# serial_4.net
KiCad netlist of a schematic drawn in Altium Designer
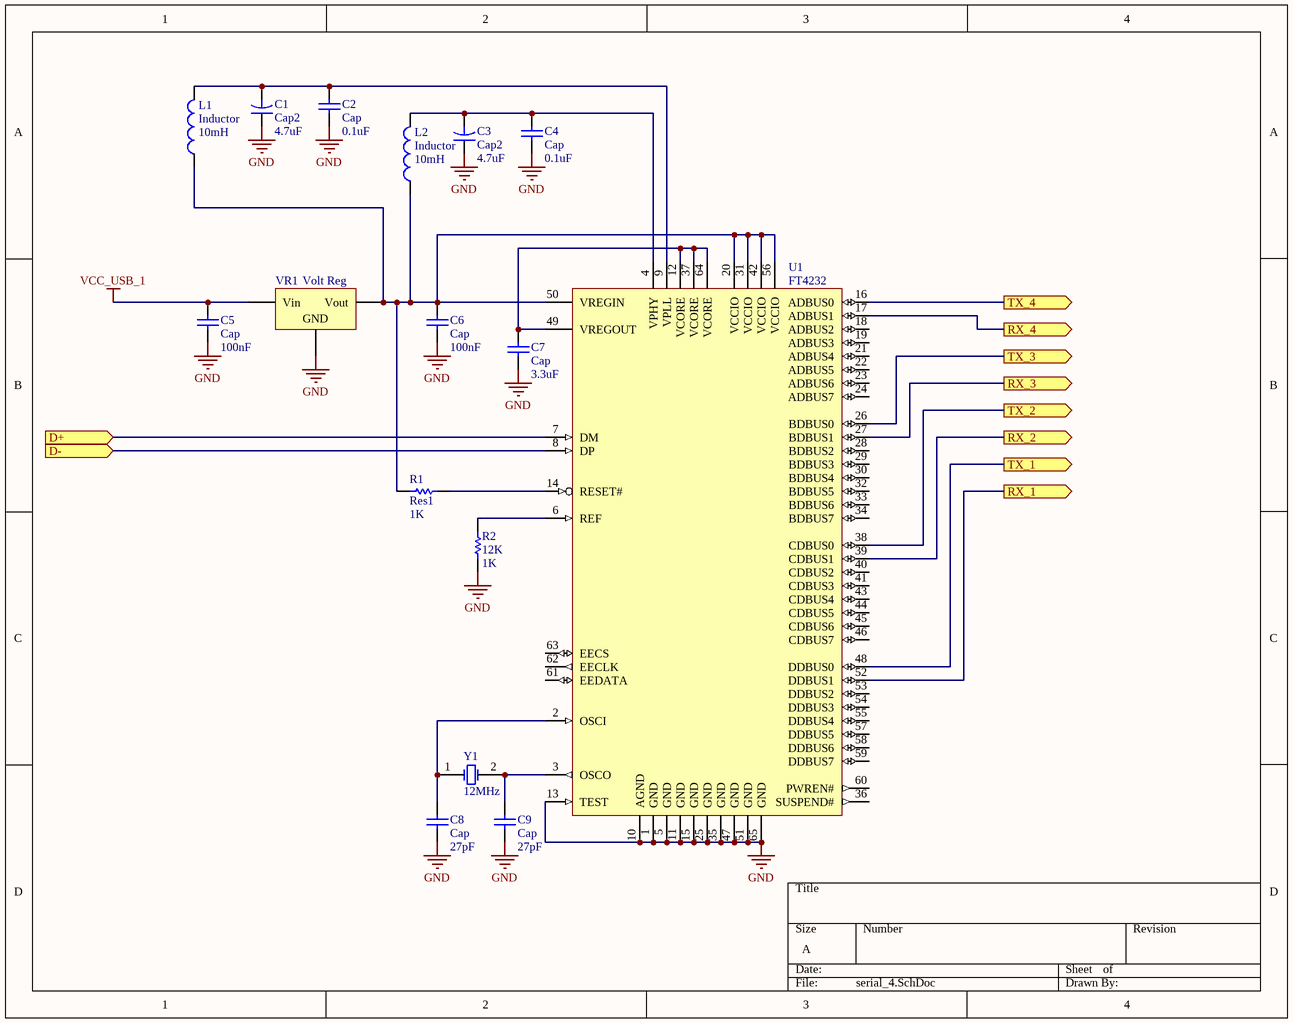
[diagram p0: serial_4.SchDoc]

(export (version "E")
  (design (tool "Eeschema 10.0.6"))
  (components
    (comp (ref "C1")
      (value "Cap2")
      (footprint "CAPR5-4X5")
      (description "Capacitor")
      (fields (field (name "ALTIUM_VALUE") "4.7uF") (field (name "PUBLISHER") "Altium Limited"))
      (libsource (lib "Miscellaneous Devices") (part "Cap2"))
    )
    (comp (ref "C2")
      (value "Cap")
      (footprint "C0805")
      (description "Capacitor")
      (fields (field (name "ALTIUM_VALUE") "0.1uF") (field (name "PUBLISHER") "Altium Limited"))
      (libsource (lib "Miscellaneous Devices") (part "Cap"))
    )
    (comp (ref "C3")
      (value "Cap2")
      (footprint "CAPR5-4X5")
      (description "Capacitor")
      (fields (field (name "ALTIUM_VALUE") "4.7uF") (field (name "PUBLISHER") "Altium Limited"))
      (libsource (lib "Miscellaneous Devices") (part "Cap2"))
    )
    (comp (ref "C4")
      (value "Cap")
      (footprint "C0805")
      (description "Capacitor")
      (fields (field (name "ALTIUM_VALUE") "0.1uF") (field (name "PUBLISHER") "Altium Limited"))
      (libsource (lib "Miscellaneous Devices") (part "Cap"))
    )
    (comp (ref "C5")
      (value "Cap")
      (footprint "C0805")
      (description "Capacitor")
      (fields (field (name "ALTIUM_VALUE") "100nF") (field (name "PUBLISHER") "Altium Limited"))
      (libsource (lib "Miscellaneous Devices") (part "Cap"))
    )
    (comp (ref "C6")
      (value "Cap")
      (footprint "C0805")
      (description "Capacitor")
      (fields (field (name "ALTIUM_VALUE") "100nF") (field (name "PUBLISHER") "Altium Limited"))
      (libsource (lib "Miscellaneous Devices") (part "Cap"))
    )
    (comp (ref "C7")
      (value "Cap")
      (footprint "C0805")
      (description "Capacitor")
      (fields (field (name "ALTIUM_VALUE") "3.3uF") (field (name "PUBLISHER") "Altium Limited"))
      (libsource (lib "Miscellaneous Devices") (part "Cap"))
    )
    (comp (ref "C8")
      (value "Cap")
      (footprint "C0805")
      (description "Capacitor")
      (fields (field (name "ALTIUM_VALUE") "27pF") (field (name "PUBLISHER") "Altium Limited"))
      (libsource (lib "Miscellaneous Devices") (part "Cap"))
    )
    (comp (ref "C9")
      (value "Cap")
      (footprint "C0805")
      (description "Capacitor")
      (fields (field (name "ALTIUM_VALUE") "27pF") (field (name "PUBLISHER") "Altium Limited"))
      (libsource (lib "Miscellaneous Devices") (part "Cap"))
    )
    (comp (ref "L1")
      (value "Inductor")
      (footprint "C0805")
      (fields (field (name "ALTIUM_VALUE") "10mH") (field (name "PUBLISHER") "Altium Limited"))
      (libsource (lib "Miscellaneous Devices") (part "Inductor"))
    )
    (comp (ref "L2")
      (value "Inductor")
      (footprint "C0805")
      (fields (field (name "ALTIUM_VALUE") "10mH") (field (name "PUBLISHER") "Altium Limited"))
      (libsource (lib "Miscellaneous Devices") (part "Inductor"))
    )
    (comp (ref "R1")
      (value "Res1")
      (footprint "0805R-1K")
      (description "Resistor")
      (fields (field (name "ALTIUM_VALUE") "1K") (field (name "PUBLISHER") "Altium Limited"))
      (libsource (lib "Miscellaneous Devices") (part "Res1"))
    )
    (comp (ref "R2")
      (value "12K")
      (footprint "0805R-12K")
      (description "Resistor")
      (fields (field (name "ALTIUM_VALUE") "1K") (field (name "PUBLISHER") "Altium Limited"))
      (libsource (lib "Miscellaneous Devices") (part "Res1"))
    )
    (comp (ref "U1")
      (value "FT4232")
      (footprint "QFN64_2_N")
      (description "Quad High Speed USB To Multipurpose UART/MPSSE IC, QFN-64, Tray")
      (fields (field (name "PUBLISHER") "Altium Limited"))
      (libsource (lib "FTDI Communication UART") (part "FT4232HQ-Tray"))
    )
    (comp (ref "VR1")
      (value "Volt Reg")
      (footprint "SOT223")
      (description "Voltage Regulator")
      (fields (field (name "PUBLISHER") "Altium Limited"))
      (libsource (lib "Miscellaneous Devices") (part "Volt Reg"))
    )
    (comp (ref "Y1")
      (value "12MHz")
      (footprint "XTAL-HC49US-7MM")
      (description "Crystal Oscillator")
      (fields (field (name "PUBLISHER") "Altium Limited"))
      (libsource (lib "Miscellaneous Devices") (part "XTAL"))
    )
  )
  (nets
    (net (code "1") (name "/D+") (class "Default")
      (node (ref "U1") (pin "7") (pinfunction "DM_7") (pintype "input"))
    )
    (net (code "2") (name "/D-") (class "Default")
      (node (ref "U1") (pin "8") (pinfunction "DP_8") (pintype "input"))
    )
    (net (code "3") (name "/RX_1") (class "Default")
      (node (ref "U1") (pin "52") (pinfunction "DDBUS1_52") (pintype "bidirectional"))
    )
    (net (code "4") (name "/RX_2") (class "Default")
      (node (ref "U1") (pin "39") (pinfunction "CDBUS1_39") (pintype "bidirectional"))
    )
    (net (code "5") (name "/RX_3") (class "Default")
      (node (ref "U1") (pin "27") (pinfunction "BDBUS1_27") (pintype "bidirectional"))
    )
    (net (code "6") (name "/RX_4") (class "Default")
      (node (ref "U1") (pin "17") (pinfunction "ADBUS1_17") (pintype "bidirectional"))
    )
    (net (code "7") (name "/TX_1") (class "Default")
      (node (ref "U1") (pin "48") (pinfunction "DDBUS0_48") (pintype "bidirectional"))
    )
    (net (code "8") (name "/TX_2") (class "Default")
      (node (ref "U1") (pin "38") (pinfunction "CDBUS0_38") (pintype "bidirectional"))
    )
    (net (code "9") (name "/TX_3") (class "Default")
      (node (ref "U1") (pin "26") (pinfunction "BDBUS0_26") (pintype "bidirectional"))
    )
    (net (code "10") (name "/TX_4") (class "Default")
      (node (ref "U1") (pin "16") (pinfunction "ADBUS0_16") (pintype "bidirectional"))
    )
    (net (code "11") (name "GND") (class "Default")
      (node (ref "C1") (pin "1") (pinfunction "1_1") (pintype "passive"))
      (node (ref "C2") (pin "1") (pinfunction "1_1") (pintype "passive"))
      (node (ref "C3") (pin "1") (pinfunction "1_1") (pintype "passive"))
      (node (ref "C4") (pin "1") (pinfunction "1_1") (pintype "passive"))
      (node (ref "C5") (pin "1") (pinfunction "1_1") (pintype "passive"))
      (node (ref "C6") (pin "1") (pinfunction "1_1") (pintype "passive"))
      (node (ref "C7") (pin "1") (pinfunction "1_1") (pintype "passive"))
      (node (ref "C8") (pin "1") (pinfunction "1_1") (pintype "passive"))
      (node (ref "C9") (pin "1") (pinfunction "1_1") (pintype "passive"))
      (node (ref "R2") (pin "1") (pinfunction "1_1") (pintype "passive"))
      (node (ref "U1") (pin "1") (pinfunction "GND_1") (pintype "power_in"))
      (node (ref "U1") (pin "10") (pinfunction "AGND_10") (pintype "power_in"))
      (node (ref "U1") (pin "11") (pinfunction "GND_11") (pintype "power_in"))
      (node (ref "U1") (pin "13") (pinfunction "TEST_13") (pintype "input"))
      (node (ref "U1") (pin "15") (pinfunction "GND_15") (pintype "power_in"))
      (node (ref "U1") (pin "25") (pinfunction "GND_25") (pintype "power_in"))
      (node (ref "U1") (pin "35") (pinfunction "GND_35") (pintype "power_in"))
      (node (ref "U1") (pin "47") (pinfunction "GND_47") (pintype "power_in"))
      (node (ref "U1") (pin "5") (pinfunction "GND_5") (pintype "power_in"))
      (node (ref "U1") (pin "51") (pinfunction "GND_51") (pintype "power_in"))
      (node (ref "U1") (pin "65") (pinfunction "GND_65") (pintype "power_in"))
      (node (ref "VR1") (pin "2") (pinfunction "GND_2") (pintype "passive"))
    )
    (net (code "12") (name "Net-(U1-OSCI)") (class "Default")
      (node (ref "C8") (pin "2") (pinfunction "2_2") (pintype "passive"))
      (node (ref "U1") (pin "2") (pinfunction "OSCI_2") (pintype "input"))
      (node (ref "Y1") (pin "1") (pinfunction "OSC1_1") (pintype "passive"))
    )
    (net (code "13") (name "Net-(U1-OSCO)") (class "Default")
      (node (ref "C9") (pin "2") (pinfunction "2_2") (pintype "passive"))
      (node (ref "U1") (pin "3") (pinfunction "OSCO_3") (pintype "output"))
      (node (ref "Y1") (pin "2") (pinfunction "OSC2_2") (pintype "passive"))
    )
    (net (code "14") (name "Net-(U1-REF)") (class "Default")
      (node (ref "R2") (pin "2") (pinfunction "2_2") (pintype "passive"))
      (node (ref "U1") (pin "6") (pinfunction "REF_6") (pintype "input"))
    )
    (net (code "15") (name "Net-(U1-RESET#)") (class "Default")
      (node (ref "R1") (pin "1") (pinfunction "1_1") (pintype "passive"))
      (node (ref "U1") (pin "14") (pinfunction "RESET#_14") (pintype "input"))
    )
    (net (code "16") (name "Net-(U1-VPHY)") (class "Default")
      (node (ref "C3") (pin "2") (pinfunction "2_2") (pintype "passive"))
      (node (ref "C4") (pin "2") (pinfunction "2_2") (pintype "passive"))
      (node (ref "L2") (pin "2") (pinfunction "2_2") (pintype "passive"))
      (node (ref "U1") (pin "4") (pinfunction "VPHY_4") (pintype "power_in"))
    )
    (net (code "17") (name "Net-(U1-VPLL)") (class "Default")
      (node (ref "C1") (pin "2") (pinfunction "2_2") (pintype "passive"))
      (node (ref "C2") (pin "2") (pinfunction "2_2") (pintype "passive"))
      (node (ref "L1") (pin "2") (pinfunction "2_2") (pintype "passive"))
      (node (ref "U1") (pin "9") (pinfunction "VPLL_9") (pintype "power_in"))
    )
    (net (code "18") (name "Net-(U1-VREGIN)") (class "Default")
      (node (ref "C6") (pin "2") (pinfunction "2_2") (pintype "passive"))
      (node (ref "L1") (pin "1") (pinfunction "1_1") (pintype "passive"))
      (node (ref "L2") (pin "1") (pinfunction "1_1") (pintype "passive"))
      (node (ref "R1") (pin "2") (pinfunction "2_2") (pintype "passive"))
      (node (ref "U1") (pin "20") (pinfunction "VCCIO_20") (pintype "power_in"))
      (node (ref "U1") (pin "31") (pinfunction "VCCIO_31") (pintype "power_in"))
      (node (ref "U1") (pin "42") (pinfunction "VCCIO_42") (pintype "power_in"))
      (node (ref "U1") (pin "50") (pinfunction "VREGIN_50") (pintype "power_in"))
      (node (ref "U1") (pin "56") (pinfunction "VCCIO_56") (pintype "power_in"))
      (node (ref "VR1") (pin "3") (pinfunction "Vout_3") (pintype "passive"))
    )
    (net (code "19") (name "Net-(U1-VREGOUT)") (class "Default")
      (node (ref "C7") (pin "2") (pinfunction "2_2") (pintype "passive"))
      (node (ref "U1") (pin "12") (pinfunction "VCORE_12") (pintype "power_in"))
      (node (ref "U1") (pin "37") (pinfunction "VCORE_37") (pintype "power_in"))
      (node (ref "U1") (pin "49") (pinfunction "VREGOUT_49") (pintype "power_in"))
      (node (ref "U1") (pin "64") (pinfunction "VCORE_64") (pintype "power_in"))
    )
    (net (code "20") (name "VCC_USB_1") (class "Default")
      (node (ref "C5") (pin "2") (pinfunction "2_2") (pintype "passive"))
      (node (ref "VR1") (pin "1") (pinfunction "Vin_1") (pintype "passive"))
    )
    (net (code "21") (name "unconnected-(U1-ADBUS2-Pad18)") (class "Default")
      (node (ref "U1") (pin "18") (pinfunction "ADBUS2_18") (pintype "bidirectional"))
    )
    (net (code "22") (name "unconnected-(U1-ADBUS3-Pad19)") (class "Default")
      (node (ref "U1") (pin "19") (pinfunction "ADBUS3_19") (pintype "bidirectional"))
    )
    (net (code "23") (name "unconnected-(U1-ADBUS4-Pad21)") (class "Default")
      (node (ref "U1") (pin "21") (pinfunction "ADBUS4_21") (pintype "bidirectional"))
    )
    (net (code "24") (name "unconnected-(U1-ADBUS5-Pad22)") (class "Default")
      (node (ref "U1") (pin "22") (pinfunction "ADBUS5_22") (pintype "bidirectional"))
    )
    (net (code "25") (name "unconnected-(U1-ADBUS6-Pad23)") (class "Default")
      (node (ref "U1") (pin "23") (pinfunction "ADBUS6_23") (pintype "bidirectional"))
    )
    (net (code "26") (name "unconnected-(U1-ADBUS7-Pad24)") (class "Default")
      (node (ref "U1") (pin "24") (pinfunction "ADBUS7_24") (pintype "bidirectional"))
    )
    (net (code "27") (name "unconnected-(U1-BDBUS2-Pad28)") (class "Default")
      (node (ref "U1") (pin "28") (pinfunction "BDBUS2_28") (pintype "bidirectional"))
    )
    (net (code "28") (name "unconnected-(U1-BDBUS3-Pad29)") (class "Default")
      (node (ref "U1") (pin "29") (pinfunction "BDBUS3_29") (pintype "bidirectional"))
    )
    (net (code "29") (name "unconnected-(U1-BDBUS4-Pad30)") (class "Default")
      (node (ref "U1") (pin "30") (pinfunction "BDBUS4_30") (pintype "bidirectional"))
    )
    (net (code "30") (name "unconnected-(U1-BDBUS5-Pad32)") (class "Default")
      (node (ref "U1") (pin "32") (pinfunction "BDBUS5_32") (pintype "bidirectional"))
    )
    (net (code "31") (name "unconnected-(U1-BDBUS6-Pad33)") (class "Default")
      (node (ref "U1") (pin "33") (pinfunction "BDBUS6_33") (pintype "bidirectional"))
    )
    (net (code "32") (name "unconnected-(U1-BDBUS7-Pad34)") (class "Default")
      (node (ref "U1") (pin "34") (pinfunction "BDBUS7_34") (pintype "bidirectional"))
    )
    (net (code "33") (name "unconnected-(U1-CDBUS2-Pad40)") (class "Default")
      (node (ref "U1") (pin "40") (pinfunction "CDBUS2_40") (pintype "bidirectional"))
    )
    (net (code "34") (name "unconnected-(U1-CDBUS3-Pad41)") (class "Default")
      (node (ref "U1") (pin "41") (pinfunction "CDBUS3_41") (pintype "bidirectional"))
    )
    (net (code "35") (name "unconnected-(U1-CDBUS4-Pad43)") (class "Default")
      (node (ref "U1") (pin "43") (pinfunction "CDBUS4_43") (pintype "bidirectional"))
    )
    (net (code "36") (name "unconnected-(U1-CDBUS5-Pad44)") (class "Default")
      (node (ref "U1") (pin "44") (pinfunction "CDBUS5_44") (pintype "bidirectional"))
    )
    (net (code "37") (name "unconnected-(U1-CDBUS6-Pad45)") (class "Default")
      (node (ref "U1") (pin "45") (pinfunction "CDBUS6_45") (pintype "bidirectional"))
    )
    (net (code "38") (name "unconnected-(U1-CDBUS7-Pad46)") (class "Default")
      (node (ref "U1") (pin "46") (pinfunction "CDBUS7_46") (pintype "bidirectional"))
    )
    (net (code "39") (name "unconnected-(U1-DDBUS2-Pad53)") (class "Default")
      (node (ref "U1") (pin "53") (pinfunction "DDBUS2_53") (pintype "bidirectional"))
    )
    (net (code "40") (name "unconnected-(U1-DDBUS3-Pad54)") (class "Default")
      (node (ref "U1") (pin "54") (pinfunction "DDBUS3_54") (pintype "bidirectional"))
    )
    (net (code "41") (name "unconnected-(U1-DDBUS4-Pad55)") (class "Default")
      (node (ref "U1") (pin "55") (pinfunction "DDBUS4_55") (pintype "bidirectional"))
    )
    (net (code "42") (name "unconnected-(U1-DDBUS5-Pad57)") (class "Default")
      (node (ref "U1") (pin "57") (pinfunction "DDBUS5_57") (pintype "bidirectional"))
    )
    (net (code "43") (name "unconnected-(U1-DDBUS6-Pad58)") (class "Default")
      (node (ref "U1") (pin "58") (pinfunction "DDBUS6_58") (pintype "bidirectional"))
    )
    (net (code "44") (name "unconnected-(U1-DDBUS7-Pad59)") (class "Default")
      (node (ref "U1") (pin "59") (pinfunction "DDBUS7_59") (pintype "bidirectional"))
    )
    (net (code "45") (name "unconnected-(U1-EECLK-Pad62)") (class "Default")
      (node (ref "U1") (pin "62") (pinfunction "EECLK_62") (pintype "output"))
    )
    (net (code "46") (name "unconnected-(U1-EECS-Pad63)") (class "Default")
      (node (ref "U1") (pin "63") (pinfunction "EECS_63") (pintype "bidirectional"))
    )
    (net (code "47") (name "unconnected-(U1-EEDATA-Pad61)") (class "Default")
      (node (ref "U1") (pin "61") (pinfunction "EEDATA_61") (pintype "bidirectional"))
    )
    (net (code "48") (name "unconnected-(U1-PWREN#-Pad60)") (class "Default")
      (node (ref "U1") (pin "60") (pinfunction "PWREN#_60") (pintype "output"))
    )
    (net (code "49") (name "unconnected-(U1-SUSPEND#-Pad36)") (class "Default")
      (node (ref "U1") (pin "36") (pinfunction "SUSPEND#_36") (pintype "output"))
    )
  )
)
